# Sheet1.net
KiCad netlist of a schematic drawn in Altium Designer
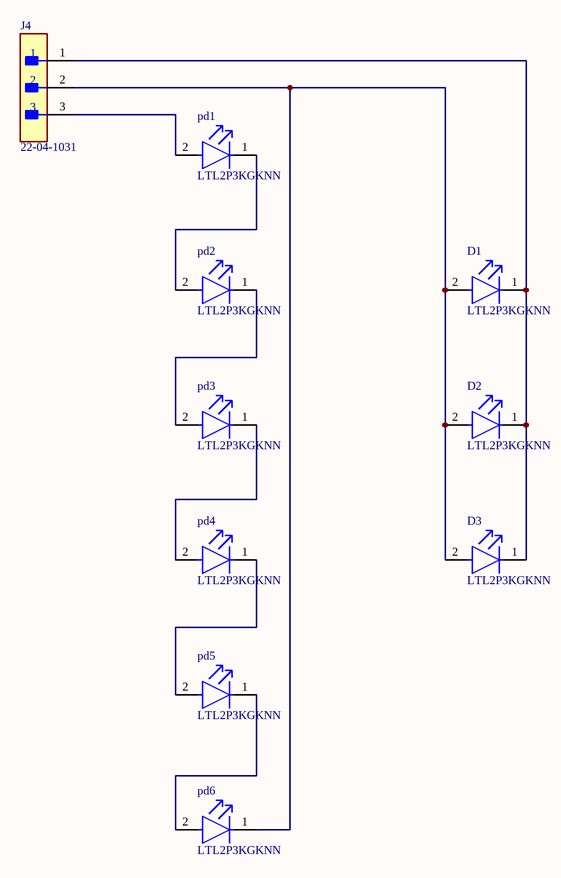
[diagram p0: Sheet1.SchDoc]

(export (version "E")
  (design (tool "Eeschema 10.0.6"))
  (components
    (comp (ref "D1")
      (value "LTL2P3KGKNN")
      (footprint "FP-LTL2P3KGKNN-MFG")
      (description "LED GREEN CLEAR T-1 3/4 T/H")
      (fields
        (field (name "MANUFACTURER") "Lite-On")
        (field (name "OCTOPART") "https://octopart.com/ltl2p3kgknn-lite-on-550036")
      )
      (libsource (lib "Altium Content Vault") (part "8706943c75ba83719d021d2fdc84c58"))
    )
    (comp (ref "D2")
      (value "LTL2P3KGKNN")
      (footprint "FP-LTL2P3KGKNN-MFG")
      (description "LED GREEN CLEAR T-1 3/4 T/H")
      (fields
        (field (name "MANUFACTURER") "Lite-On")
        (field (name "OCTOPART") "https://octopart.com/ltl2p3kgknn-lite-on-550036")
      )
      (libsource (lib "Altium Content Vault") (part "8706943c75ba83719d021d2fdc84c58"))
    )
    (comp (ref "D3")
      (value "LTL2P3KGKNN")
      (footprint "FP-LTL2P3KGKNN-MFG")
      (description "LED GREEN CLEAR T-1 3/4 T/H")
      (fields
        (field (name "MANUFACTURER") "Lite-On")
        (field (name "OCTOPART") "https://octopart.com/ltl2p3kgknn-lite-on-550036")
      )
      (libsource (lib "Altium Content Vault") (part "8706943c75ba83719d021d2fdc84c58"))
    )
    (comp (ref "J4")
      (value "22-04-1031")
      (footprint "FP-22-04-1031-MFG")
      (description "CONN HEADER VERT 3POS 2.5MM")
      (libsource (lib "Altium Content Vault") (part "0d3f023dd272f625e17a2be33dea85f"))
    )
    (comp (ref "pd1")
      (value "LTL2P3KGKNN")
      (footprint "FP-LTL2P3KGKNN-MFG")
      (description "LED GREEN CLEAR T-1 3/4 T/H")
      (fields
        (field (name "MANUFACTURER") "Lite-On")
        (field (name "OCTOPART") "https://octopart.com/ltl2p3kgknn-lite-on-550036")
      )
      (libsource (lib "Altium Content Vault") (part "8706943c75ba83719d021d2fdc84c58"))
    )
    (comp (ref "pd2")
      (value "LTL2P3KGKNN")
      (footprint "FP-LTL2P3KGKNN-MFG")
      (description "LED GREEN CLEAR T-1 3/4 T/H")
      (fields
        (field (name "MANUFACTURER") "Lite-On")
        (field (name "OCTOPART") "https://octopart.com/ltl2p3kgknn-lite-on-550036")
      )
      (libsource (lib "Altium Content Vault") (part "8706943c75ba83719d021d2fdc84c58"))
    )
    (comp (ref "pd3")
      (value "LTL2P3KGKNN")
      (footprint "FP-LTL2P3KGKNN-MFG")
      (description "LED GREEN CLEAR T-1 3/4 T/H")
      (fields
        (field (name "MANUFACTURER") "Lite-On")
        (field (name "OCTOPART") "https://octopart.com/ltl2p3kgknn-lite-on-550036")
      )
      (libsource (lib "Altium Content Vault") (part "8706943c75ba83719d021d2fdc84c58"))
    )
    (comp (ref "pd4")
      (value "LTL2P3KGKNN")
      (footprint "FP-LTL2P3KGKNN-MFG")
      (description "LED GREEN CLEAR T-1 3/4 T/H")
      (fields
        (field (name "MANUFACTURER") "Lite-On")
        (field (name "OCTOPART") "https://octopart.com/ltl2p3kgknn-lite-on-550036")
      )
      (libsource (lib "Altium Content Vault") (part "8706943c75ba83719d021d2fdc84c58"))
    )
    (comp (ref "pd5")
      (value "LTL2P3KGKNN")
      (footprint "FP-LTL2P3KGKNN-MFG")
      (description "LED GREEN CLEAR T-1 3/4 T/H")
      (fields
        (field (name "MANUFACTURER") "Lite-On")
        (field (name "OCTOPART") "https://octopart.com/ltl2p3kgknn-lite-on-550036")
      )
      (libsource (lib "Altium Content Vault") (part "8706943c75ba83719d021d2fdc84c58"))
    )
    (comp (ref "pd6")
      (value "LTL2P3KGKNN")
      (footprint "FP-LTL2P3KGKNN-MFG")
      (description "LED GREEN CLEAR T-1 3/4 T/H")
      (fields
        (field (name "MANUFACTURER") "Lite-On")
        (field (name "OCTOPART") "https://octopart.com/ltl2p3kgknn-lite-on-550036")
      )
      (libsource (lib "Altium Content Vault") (part "8706943c75ba83719d021d2fdc84c58"))
    )
  )
  (nets
    (net (code "1") (name "Net-(D1-A)") (class "Default")
      (node (ref "D1") (pin "2") (pinfunction "A_2") (pintype "passive"))
      (node (ref "D2") (pin "2") (pinfunction "A_2") (pintype "passive"))
      (node (ref "D3") (pin "2") (pinfunction "A_2") (pintype "passive"))
      (node (ref "J4") (pin "2") (pinfunction "2_2") (pintype "passive"))
      (node (ref "pd6") (pin "1") (pinfunction "C_1") (pintype "passive"))
    )
    (net (code "2") (name "Net-(D1-C)") (class "Default")
      (node (ref "D1") (pin "1") (pinfunction "C_1") (pintype "passive"))
      (node (ref "D2") (pin "1") (pinfunction "C_1") (pintype "passive"))
      (node (ref "D3") (pin "1") (pinfunction "C_1") (pintype "passive"))
      (node (ref "J4") (pin "1") (pinfunction "1_1") (pintype "passive"))
    )
    (net (code "3") (name "Net-(pd1-A)") (class "Default")
      (node (ref "J4") (pin "3") (pinfunction "3_3") (pintype "passive"))
      (node (ref "pd1") (pin "2") (pinfunction "A_2") (pintype "passive"))
    )
    (net (code "4") (name "Net-(pd1-C)") (class "Default")
      (node (ref "pd1") (pin "1") (pinfunction "C_1") (pintype "passive"))
      (node (ref "pd2") (pin "2") (pinfunction "A_2") (pintype "passive"))
    )
    (net (code "5") (name "Net-(pd2-C)") (class "Default")
      (node (ref "pd2") (pin "1") (pinfunction "C_1") (pintype "passive"))
      (node (ref "pd3") (pin "2") (pinfunction "A_2") (pintype "passive"))
    )
    (net (code "6") (name "Net-(pd3-C)") (class "Default")
      (node (ref "pd3") (pin "1") (pinfunction "C_1") (pintype "passive"))
      (node (ref "pd4") (pin "2") (pinfunction "A_2") (pintype "passive"))
    )
    (net (code "7") (name "Net-(pd4-C)") (class "Default")
      (node (ref "pd4") (pin "1") (pinfunction "C_1") (pintype "passive"))
      (node (ref "pd5") (pin "2") (pinfunction "A_2") (pintype "passive"))
    )
    (net (code "8") (name "Net-(pd5-C)") (class "Default")
      (node (ref "pd5") (pin "1") (pinfunction "C_1") (pintype "passive"))
      (node (ref "pd6") (pin "2") (pinfunction "A_2") (pintype "passive"))
    )
  )
)
